# rf_bms.net
KiCad netlist of a schematic drawn in Altium Designer
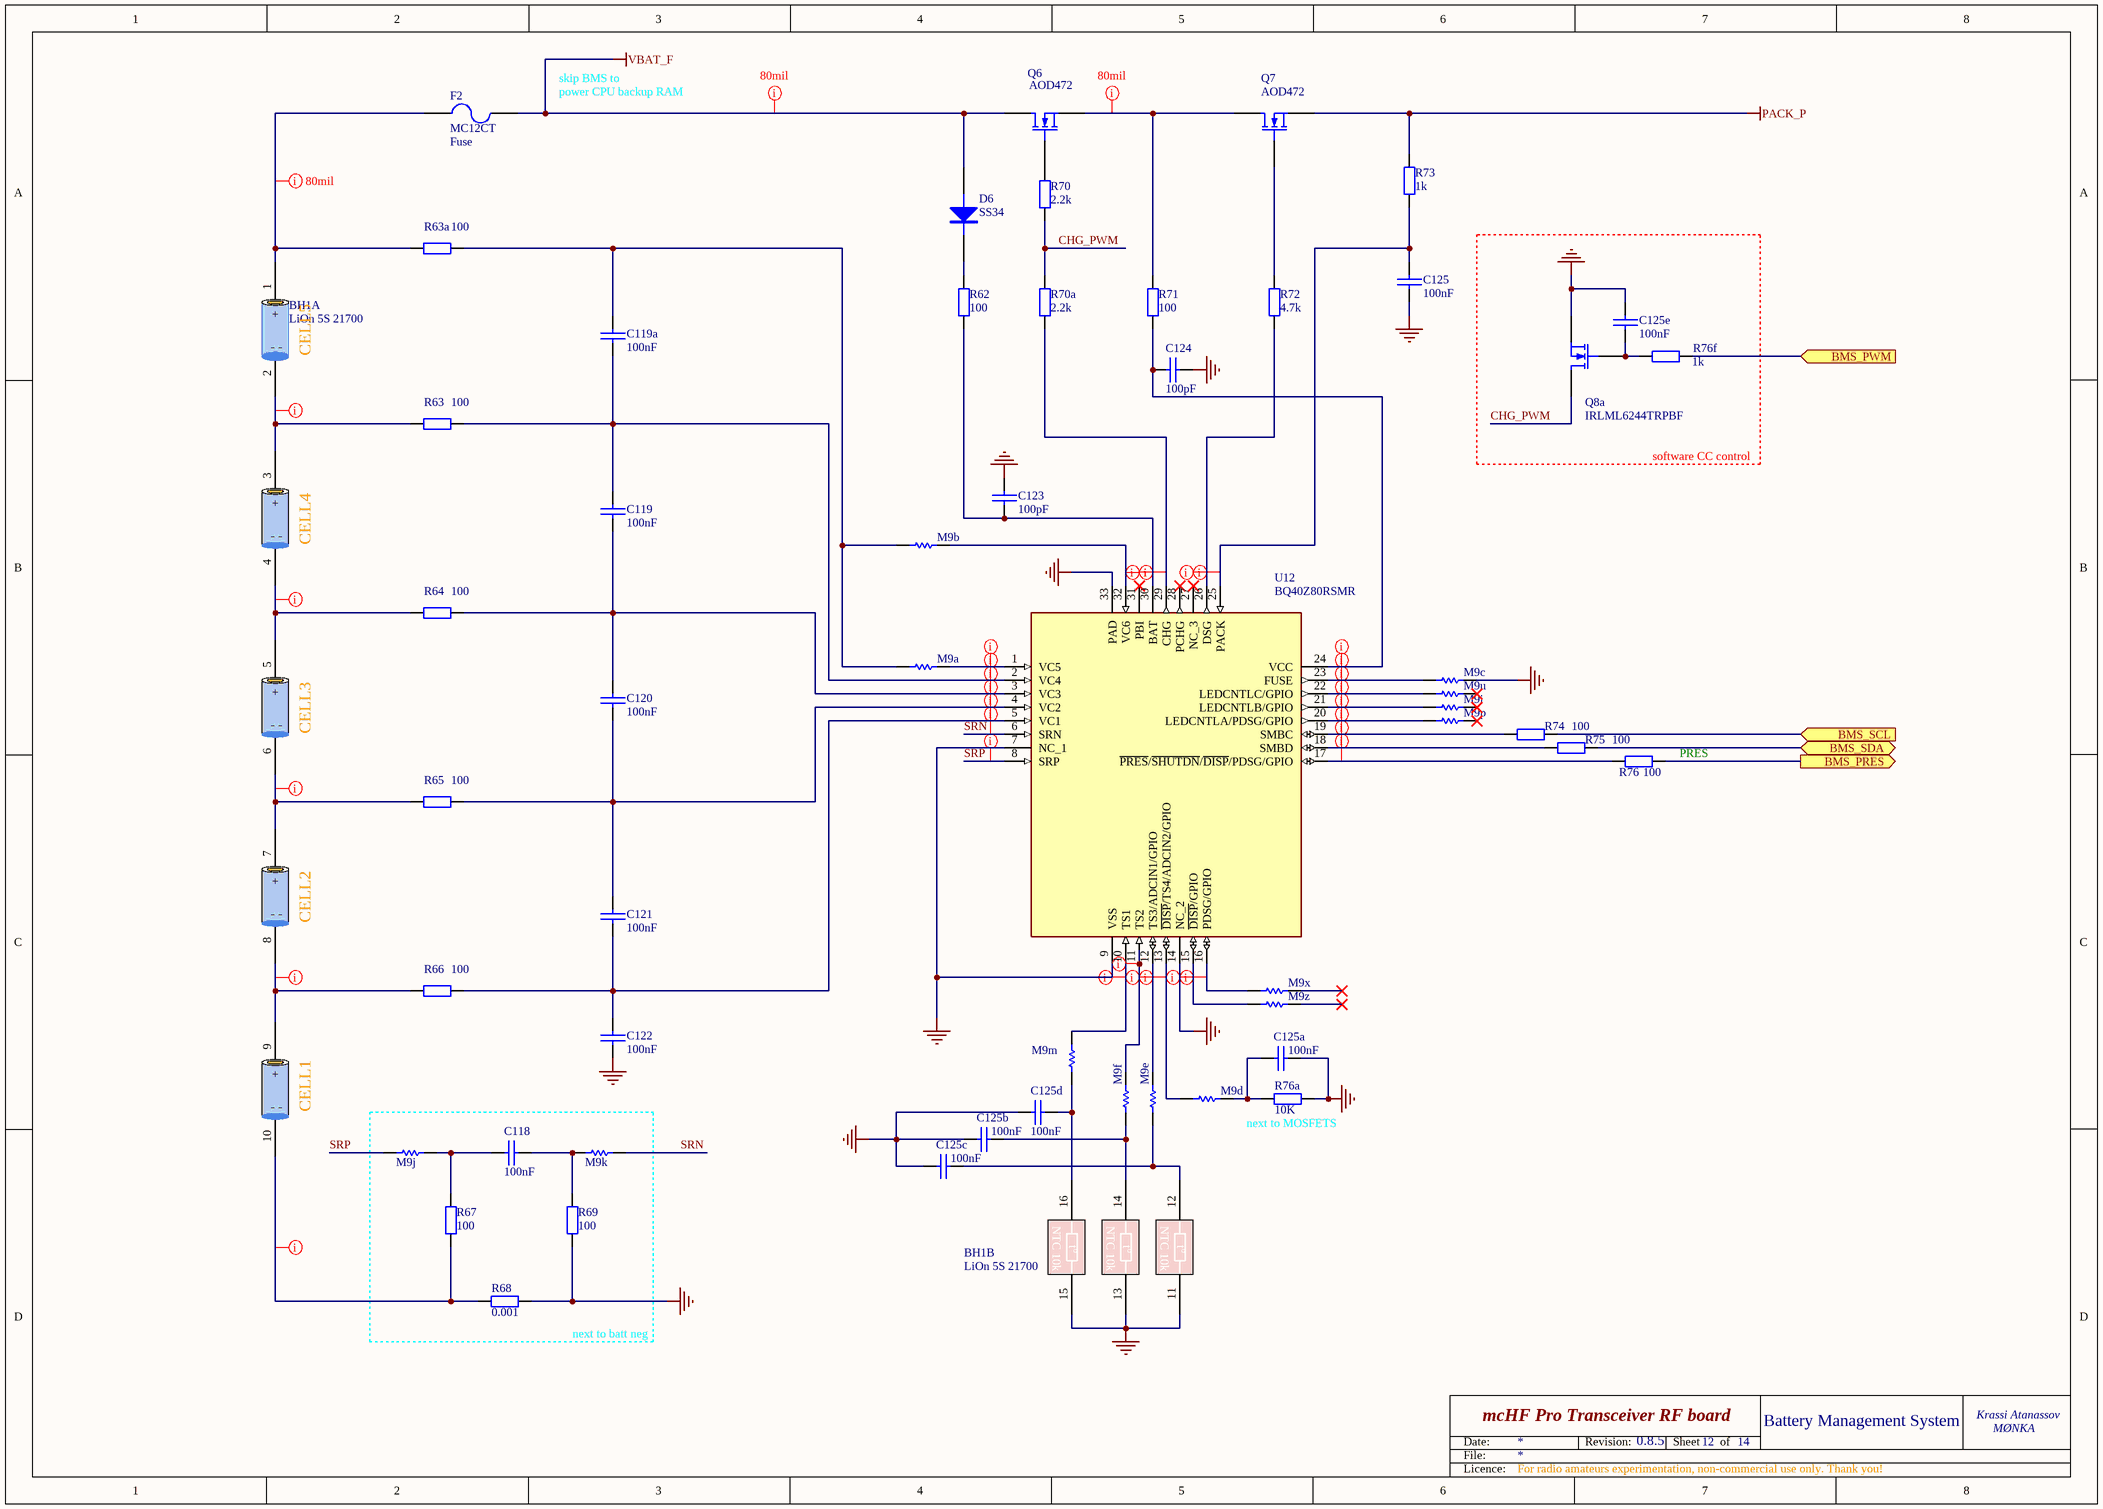
[diagram p0: rf_bms.SchDoc]

(export (version "E")
  (design (tool "Eeschema 10.0.6"))
  (components
    (comp (ref "BH1")
      (value "LiOn 5S 21700")
      (footprint "BATT_HOLDER_5S")
      (description "LiOn 21700 5S Holder")
      (libsource (lib "") (part "BATT_HOLDER_5S_21700_1"))
    )
    (comp (ref "C118")
      (value "100nF")
      (footprint "0805")
      (description "Capacitor")
      (fields (field (name "VOLTAGE") "100V"))
      (libsource (lib "mcHF_rf") (part "CAP"))
    )
    (comp (ref "C119")
      (value "100nF")
      (footprint "0805")
      (description "Capacitor")
      (fields (field (name "VOLTAGE") "100V"))
      (libsource (lib "mcHF_rf") (part "CAP"))
    )
    (comp (ref "C119a")
      (value "100nF")
      (footprint "0805")
      (description "Capacitor")
      (fields (field (name "VOLTAGE") "100V"))
      (libsource (lib "mcHF_rf") (part "CAP"))
    )
    (comp (ref "C120")
      (value "100nF")
      (footprint "0805")
      (description "Capacitor")
      (fields (field (name "VOLTAGE") "100V"))
      (libsource (lib "mcHF_rf") (part "CAP"))
    )
    (comp (ref "C121")
      (value "100nF")
      (footprint "0805")
      (description "Capacitor")
      (fields (field (name "VOLTAGE") "100V"))
      (libsource (lib "mcHF_rf") (part "CAP"))
    )
    (comp (ref "C122")
      (value "100nF")
      (footprint "0805")
      (description "Capacitor")
      (fields (field (name "VOLTAGE") "100V"))
      (libsource (lib "mcHF_rf") (part "CAP"))
    )
    (comp (ref "C123")
      (value "100pF")
      (footprint "0805")
      (description "Capacitor")
      (fields (field (name "VOLTAGE") "100V"))
      (libsource (lib "mcHF_rf") (part "CAP"))
    )
    (comp (ref "C124")
      (value "100pF")
      (footprint "0805")
      (description "Capacitor")
      (fields (field (name "VOLTAGE") "100V"))
      (libsource (lib "mcHF_rf") (part "CAP"))
    )
    (comp (ref "C125")
      (value "100nF")
      (footprint "0805")
      (description "Capacitor")
      (fields (field (name "VOLTAGE") "100V"))
      (libsource (lib "mcHF_rf") (part "CAP"))
    )
    (comp (ref "C125a")
      (value "100nF")
      (footprint "0805")
      (description "Capacitor")
      (fields (field (name "VOLTAGE") "100V"))
      (libsource (lib "mcHF_rf") (part "CAP"))
    )
    (comp (ref "C125b")
      (value "100nF")
      (footprint "0805")
      (description "Capacitor")
      (fields (field (name "VOLTAGE") "100V"))
      (libsource (lib "mcHF_rf") (part "CAP"))
    )
    (comp (ref "C125c")
      (value "100nF")
      (footprint "0805")
      (description "Capacitor")
      (fields (field (name "VOLTAGE") "100V"))
      (libsource (lib "mcHF_rf") (part "CAP"))
    )
    (comp (ref "C125d")
      (value "100nF")
      (footprint "0805")
      (description "Capacitor")
      (fields (field (name "VOLTAGE") "100V"))
      (libsource (lib "mcHF_rf") (part "CAP"))
    )
    (comp (ref "C125e")
      (value "100nF")
      (footprint "0805")
      (description "Capacitor")
      (fields (field (name "VOLTAGE") "100V"))
      (libsource (lib "mcHF_rf") (part "CAP"))
    )
    (comp (ref "D6")
      (value "SS34")
      (footprint "DO214")
      (description "DIODE, SCHOTTKY, 1A, 60V, SOD-123F")
      (libsource (lib "mcHF_rf") (part "PMEG6010CEH"))
    )
    (comp (ref "F2")
      (value "MC12CT")
      (footprint "1206")
      (description "Fuse")
      (fields (field (name "FUNCTION") "Fuse"))
      (libsource (lib "mcHF_rf") (part "Fuse"))
    )
    (comp (ref "M9a")
      (value "0")
      (footprint "SB_0603_10")
      (description "Link")
      (fields (field (name "PUBLISHER") "Altium Limited"))
      (libsource (lib "__ui") (part "Link"))
    )
    (comp (ref "M9b")
      (value "0")
      (footprint "SB_0603_10")
      (description "Link")
      (fields (field (name "PUBLISHER") "Altium Limited"))
      (libsource (lib "__ui") (part "Link"))
    )
    (comp (ref "M9c")
      (value "0")
      (footprint "SB_0603_10")
      (description "Link")
      (fields (field (name "PUBLISHER") "Altium Limited"))
      (libsource (lib "__ui") (part "Link"))
    )
    (comp (ref "M9d")
      (value "0")
      (footprint "SB_0603_10")
      (description "Link")
      (fields (field (name "PUBLISHER") "Altium Limited"))
      (libsource (lib "__ui") (part "Link"))
    )
    (comp (ref "M9e")
      (value "0")
      (footprint "SB_0603_10")
      (description "Link")
      (fields (field (name "PUBLISHER") "Altium Limited"))
      (libsource (lib "__ui") (part "Link"))
    )
    (comp (ref "M9f")
      (value "0")
      (footprint "SB_0603_10")
      (description "Link")
      (fields (field (name "PUBLISHER") "Altium Limited"))
      (libsource (lib "__ui") (part "Link"))
    )
    (comp (ref "M9i")
      (value "0")
      (footprint "SB_0603_10")
      (description "Link")
      (fields (field (name "PUBLISHER") "Altium Limited"))
      (libsource (lib "__ui") (part "Link"))
    )
    (comp (ref "M9j")
      (value "0")
      (footprint "SB_0603_10")
      (description "Link")
      (fields (field (name "PUBLISHER") "Altium Limited"))
      (libsource (lib "__ui") (part "Link"))
    )
    (comp (ref "M9k")
      (value "0")
      (footprint "SB_0603_10")
      (description "Link")
      (fields (field (name "PUBLISHER") "Altium Limited"))
      (libsource (lib "__ui") (part "Link"))
    )
    (comp (ref "M9m")
      (value "0")
      (footprint "SB_0603_10")
      (description "Link")
      (fields (field (name "PUBLISHER") "Altium Limited"))
      (libsource (lib "__ui") (part "Link"))
    )
    (comp (ref "M9p")
      (value "0")
      (footprint "SB_0603_10")
      (description "Link")
      (fields (field (name "PUBLISHER") "Altium Limited"))
      (libsource (lib "__ui") (part "Link"))
    )
    (comp (ref "M9u")
      (value "0")
      (footprint "SB_0603_10")
      (description "Link")
      (fields (field (name "PUBLISHER") "Altium Limited"))
      (libsource (lib "__ui") (part "Link"))
    )
    (comp (ref "M9x")
      (value "0")
      (footprint "SB_0603_10")
      (description "Link")
      (fields (field (name "PUBLISHER") "Altium Limited"))
      (libsource (lib "__ui") (part "Link"))
    )
    (comp (ref "M9z")
      (value "0")
      (footprint "SB_0603_10")
      (description "Link")
      (fields (field (name "PUBLISHER") "Altium Limited"))
      (libsource (lib "__ui") (part "Link"))
    )
    (comp (ref "Q6")
      (value "AOD472")
      (footprint "TO-252")
      (description "N-Channel Enhancement Mode Field Effect Transistor, TO-252")
      (libsource (lib "__rf") (part "AOD472"))
    )
    (comp (ref "Q7")
      (value "AOD472")
      (footprint "TO-252")
      (description "N-Channel Enhancement Mode Field Effect Transistor, TO-252")
      (libsource (lib "__rf") (part "AOD472"))
    )
    (comp (ref "Q8a")
      (value "IRLML6244TRPBF")
      (footprint "SOT-23-Pro")
      (description "N-Channel MOSFET")
      (libsource (lib "mcHF_ui_b") (part "MOSFET-N"))
    )
    (comp (ref "R62")
      (value "100")
      (footprint "0805")
      (description "Resistor")
      (libsource (lib "mcHF_rf") (part "RES"))
    )
    (comp (ref "R63")
      (value "100")
      (footprint "0805")
      (description "Resistor")
      (libsource (lib "") (part "RES_2"))
    )
    (comp (ref "R63a")
      (value "100")
      (footprint "0805")
      (description "Resistor")
      (libsource (lib "") (part "RES_2"))
    )
    (comp (ref "R64")
      (value "100")
      (footprint "0805")
      (description "Resistor")
      (libsource (lib "") (part "RES_2"))
    )
    (comp (ref "R65")
      (value "100")
      (footprint "0805")
      (description "Resistor")
      (libsource (lib "") (part "RES_2"))
    )
    (comp (ref "R66")
      (value "100")
      (footprint "0805")
      (description "Resistor")
      (libsource (lib "") (part "RES_2"))
    )
    (comp (ref "R67")
      (value "100")
      (footprint "0805")
      (description "Resistor")
      (libsource (lib "mcHF_ui_b") (part "RES"))
    )
    (comp (ref "R68")
      (value "0.001")
      (footprint "2512")
      (description "Resistor")
      (libsource (lib "") (part "RES_1"))
    )
    (comp (ref "R69")
      (value "100")
      (footprint "0805")
      (description "Resistor")
      (libsource (lib "mcHF_ui_b") (part "RES"))
    )
    (comp (ref "R70")
      (value "2.2k")
      (footprint "0805")
      (description "Resistor")
      (libsource (lib "") (part "RES_1"))
    )
    (comp (ref "R70a")
      (value "2.2k")
      (footprint "0805")
      (description "Resistor")
      (libsource (lib "") (part "RES_1"))
    )
    (comp (ref "R71")
      (value "100")
      (footprint "0805")
      (description "Resistor")
      (libsource (lib "mcHF_ui_b") (part "RES"))
    )
    (comp (ref "R72")
      (value "4.7k")
      (footprint "0805")
      (description "Resistor")
      (libsource (lib "") (part "RES_1"))
    )
    (comp (ref "R73")
      (value "1k")
      (footprint "0805")
      (description "Resistor")
      (libsource (lib "") (part "RES_1"))
    )
    (comp (ref "R74")
      (value "100")
      (footprint "0805")
      (description "Resistor")
      (libsource (lib "") (part "RES_2"))
    )
    (comp (ref "R75")
      (value "100")
      (footprint "0805")
      (description "Resistor")
      (libsource (lib "") (part "RES_2"))
    )
    (comp (ref "R76")
      (value "100")
      (footprint "0805")
      (description "Resistor")
      (libsource (lib "") (part "RES_2"))
    )
    (comp (ref "R76a")
      (value "10K")
      (footprint "0805")
      (description "Resistor")
      (libsource (lib "") (part "RES_1"))
    )
    (comp (ref "R76f")
      (value "1k")
      (footprint "0805")
      (description "Resistor")
      (libsource (lib "") (part "RES_2"))
    )
    (comp (ref "U12")
      (value "BQ40Z80RSMR")
      (footprint "SamacSys:QFN40P400X400X100-33N-D")
      (description "Hardware")
      (fields (field (name "MOUSER PART NUMBER") "595-BQ40Z80RSMR"))
      (libsource (lib "SamacSys") (part "BQ40Z80RSMR"))
    )
  )
  (nets
    (net (code "1") (name "/BMS_PRES") (class "Default")
      (node (ref "R76") (pin "2") (pinfunction "2_2") (pintype "passive"))
    )
    (net (code "2") (name "/BMS_PWM") (class "Default")
      (node (ref "R76f") (pin "2") (pinfunction "2_2") (pintype "passive"))
    )
    (net (code "3") (name "/BMS_SCL") (class "Default")
      (node (ref "R74") (pin "2") (pinfunction "2_2") (pintype "passive"))
    )
    (net (code "4") (name "/BMS_SDA") (class "Default")
      (node (ref "R75") (pin "2") (pinfunction "2_2") (pintype "passive"))
    )
    (net (code "5") (name "/CHG_PWM") (class "Default")
      (node (ref "Q8a") (pin "3") (pinfunction "D_3") (pintype "passive"))
      (node (ref "R70") (pin "1") (pinfunction "1_1") (pintype "passive"))
      (node (ref "R70a") (pin "2") (pinfunction "2_2") (pintype "passive"))
    )
    (net (code "6") (name "/SRN") (class "Default")
      (node (ref "M9k") (pin "1") (pinfunction "1_1") (pintype "passive"))
      (node (ref "U12") (pin "6") (pinfunction "SRN_6") (pintype "input"))
    )
    (net (code "7") (name "/SRP") (class "Default")
      (node (ref "M9j") (pin "2") (pinfunction "2_2") (pintype "passive"))
      (node (ref "U12") (pin "8") (pinfunction "SRP_8") (pintype "input"))
    )
    (net (code "8") (name "GND") (class "Default")
      (node (ref "BH1") (pin "11") (pintype "passive"))
      (node (ref "BH1") (pin "13") (pintype "passive"))
      (node (ref "BH1") (pin "15") (pintype "passive"))
      (node (ref "C122") (pin "2") (pinfunction "2_2") (pintype "passive"))
      (node (ref "C123") (pin "1") (pinfunction "1_1") (pintype "passive"))
      (node (ref "C124") (pin "1") (pinfunction "1_1") (pintype "passive"))
      (node (ref "C125") (pin "2") (pinfunction "2_2") (pintype "passive"))
      (node (ref "C125a") (pin "1") (pinfunction "1_1") (pintype "passive"))
      (node (ref "C125b") (pin "2") (pinfunction "2_2") (pintype "passive"))
      (node (ref "C125c") (pin "2") (pinfunction "2_2") (pintype "passive"))
      (node (ref "C125d") (pin "2") (pinfunction "2_2") (pintype "passive"))
      (node (ref "C125e") (pin "2") (pinfunction "2_2") (pintype "passive"))
      (node (ref "M9c") (pin "2") (pinfunction "2_2") (pintype "passive"))
      (node (ref "Q8a") (pin "2") (pinfunction "S_2") (pintype "passive"))
      (node (ref "R68") (pin "2") (pinfunction "2_2") (pintype "passive"))
      (node (ref "R69") (pin "2") (pinfunction "2_2") (pintype "passive"))
      (node (ref "R76a") (pin "2") (pinfunction "2_2") (pintype "passive"))
      (node (ref "U12") (pin "14") (pinfunction "NC_2_14") (pintype "passive"))
      (node (ref "U12") (pin "33") (pinfunction "PAD_33") (pintype "power_in"))
      (node (ref "U12") (pin "7") (pinfunction "NC_1_7") (pintype "passive"))
      (node (ref "U12") (pin "9") (pinfunction "VSS_9") (pintype "power_in"))
    )
    (net (code "9") (name "Net-(BH1-Pad12)") (class "Default")
      (node (ref "BH1") (pin "12") (pintype "passive"))
      (node (ref "C125c") (pin "1") (pinfunction "1_1") (pintype "passive"))
      (node (ref "M9e") (pin "2") (pinfunction "2_2") (pintype "passive"))
    )
    (net (code "10") (name "Net-(BH1-Pad14)") (class "Default")
      (node (ref "BH1") (pin "14") (pintype "passive"))
      (node (ref "C125b") (pin "1") (pinfunction "1_1") (pintype "passive"))
      (node (ref "M9f") (pin "2") (pinfunction "2_2") (pintype "passive"))
    )
    (net (code "11") (name "Net-(BH1-Pad16)") (class "Default")
      (node (ref "BH1") (pin "16") (pintype "passive"))
      (node (ref "C125d") (pin "1") (pinfunction "1_1") (pintype "passive"))
      (node (ref "M9m") (pin "1") (pinfunction "1_1") (pintype "passive"))
    )
    (net (code "12") (name "Net-(BH1A-+-Pad1)") (class "Default")
      (node (ref "BH1") (pin "1") (pinfunction "+_1") (pintype "passive"))
      (node (ref "F2") (pin "1") (pinfunction "1_1") (pintype "passive"))
      (node (ref "R63a") (pin "2") (pinfunction "2_2") (pintype "passive"))
    )
    (net (code "13") (name "Net-(BH1A-+-Pad3)") (class "Default")
      (node (ref "BH1") (pin "2") (pinfunction "¦_2") (pintype "passive"))
      (node (ref "BH1") (pin "3") (pinfunction "+_3") (pintype "passive"))
      (node (ref "R63") (pin "2") (pinfunction "2_2") (pintype "passive"))
    )
    (net (code "14") (name "Net-(BH1A-+-Pad5)") (class "Default")
      (node (ref "BH1") (pin "4") (pinfunction "¦_4") (pintype "passive"))
      (node (ref "BH1") (pin "5") (pinfunction "+_5") (pintype "passive"))
      (node (ref "R64") (pin "2") (pinfunction "2_2") (pintype "passive"))
    )
    (net (code "15") (name "Net-(BH1A-+-Pad7)") (class "Default")
      (node (ref "BH1") (pin "6") (pinfunction "¦_6") (pintype "passive"))
      (node (ref "BH1") (pin "7") (pinfunction "+_7") (pintype "passive"))
      (node (ref "R65") (pin "2") (pinfunction "2_2") (pintype "passive"))
    )
    (net (code "16") (name "Net-(BH1A-+-Pad9)") (class "Default")
      (node (ref "BH1") (pin "8") (pinfunction "¦_8") (pintype "passive"))
      (node (ref "BH1") (pin "9") (pinfunction "+_9") (pintype "passive"))
      (node (ref "R66") (pin "2") (pinfunction "2_2") (pintype "passive"))
    )
    (net (code "17") (name "Net-(BH1A-¦-Pad10)") (class "Default")
      (node (ref "BH1") (pin "10") (pinfunction "¦_10") (pintype "passive"))
      (node (ref "R67") (pin "2") (pinfunction "2_2") (pintype "passive"))
      (node (ref "R68") (pin "1") (pinfunction "1_1") (pintype "passive"))
    )
    (net (code "18") (name "Net-(C118-Pad1)") (class "Default")
      (node (ref "C118") (pin "1") (pinfunction "1_1") (pintype "passive"))
      (node (ref "M9k") (pin "2") (pinfunction "2_2") (pintype "passive"))
      (node (ref "R69") (pin "1") (pinfunction "1_1") (pintype "passive"))
    )
    (net (code "19") (name "Net-(C118-Pad2)") (class "Default")
      (node (ref "C118") (pin "2") (pinfunction "2_2") (pintype "passive"))
      (node (ref "M9j") (pin "1") (pinfunction "1_1") (pintype "passive"))
      (node (ref "R67") (pin "1") (pinfunction "1_1") (pintype "passive"))
    )
    (net (code "20") (name "Net-(C119a-Pad1)") (class "Default")
      (node (ref "C119a") (pin "1") (pinfunction "1_1") (pintype "passive"))
      (node (ref "M9a") (pin "1") (pinfunction "1_1") (pintype "passive"))
      (node (ref "M9b") (pin "1") (pinfunction "1_1") (pintype "passive"))
      (node (ref "R63a") (pin "1") (pinfunction "1_1") (pintype "passive"))
    )
    (net (code "21") (name "Net-(C125a-Pad2)") (class "Default")
      (node (ref "C125a") (pin "2") (pinfunction "2_2") (pintype "passive"))
      (node (ref "M9d") (pin "2") (pinfunction "2_2") (pintype "passive"))
      (node (ref "R76a") (pin "1") (pinfunction "1_1") (pintype "passive"))
    )
    (net (code "22") (name "Net-(D6-K)") (class "Default")
      (node (ref "D6") (pin "2") (pinfunction "K_2") (pintype "passive"))
      (node (ref "R62") (pin "2") (pinfunction "2_2") (pintype "passive"))
    )
    (net (code "23") (name "Net-(Q6-G)") (class "Default")
      (node (ref "Q6") (pin "1") (pinfunction "G_1") (pintype "passive"))
      (node (ref "R70") (pin "2") (pinfunction "2_2") (pintype "passive"))
    )
    (net (code "24") (name "Net-(Q6-S)") (class "Default")
      (node (ref "Q6") (pin "3") (pinfunction "S_3") (pintype "passive"))
      (node (ref "Q7") (pin "2") (pinfunction "D_2") (pintype "passive"))
      (node (ref "R71") (pin "1") (pinfunction "1_1") (pintype "passive"))
    )
    (net (code "25") (name "Net-(Q7-G)") (class "Default")
      (node (ref "Q7") (pin "1") (pinfunction "G_1") (pintype "passive"))
      (node (ref "R72") (pin "2") (pinfunction "2_2") (pintype "passive"))
    )
    (net (code "26") (name "Net-(Q8a-G)") (class "Default")
      (node (ref "C125e") (pin "1") (pinfunction "1_1") (pintype "passive"))
      (node (ref "Q8a") (pin "1") (pinfunction "G_1") (pintype "passive"))
      (node (ref "R76f") (pin "1") (pinfunction "1_1") (pintype "passive"))
    )
    (net (code "27") (name "Net-(U12-BAT)") (class "Default")
      (node (ref "C123") (pin "2") (pinfunction "2_2") (pintype "passive"))
      (node (ref "R62") (pin "1") (pinfunction "1_1") (pintype "passive"))
      (node (ref "U12") (pin "30") (pinfunction "BAT_30") (pintype "power_in"))
    )
    (net (code "28") (name "Net-(U12-CHG)") (class "Default")
      (node (ref "R70a") (pin "1") (pinfunction "1_1") (pintype "passive"))
      (node (ref "U12") (pin "29") (pinfunction "CHG_29") (pintype "output"))
    )
    (net (code "29") (name "Net-(U12-DSG)") (class "Default")
      (node (ref "R72") (pin "1") (pinfunction "1_1") (pintype "passive"))
      (node (ref "U12") (pin "26") (pinfunction "DSG_26") (pintype "output"))
    )
    (net (code "30") (name "Net-(U12-FUSE)") (class "Default")
      (node (ref "M9c") (pin "1") (pinfunction "1_1") (pintype "passive"))
      (node (ref "U12") (pin "23") (pinfunction "FUSE_23") (pintype "output"))
    )
    (net (code "31") (name "Net-(U12-LEDCNTLA{slash}PDSG{slash}GPIO)") (class "Default")
      (node (ref "M9p") (pin "1") (pinfunction "1_1") (pintype "passive"))
      (node (ref "U12") (pin "20") (pinfunction "LEDCNTLA/PDSG/GPIO_20") (pintype "output"))
    )
    (net (code "32") (name "Net-(U12-LEDCNTLB{slash}GPIO)") (class "Default")
      (node (ref "M9i") (pin "1") (pinfunction "1_1") (pintype "passive"))
      (node (ref "U12") (pin "21") (pinfunction "LEDCNTLB/GPIO_21") (pintype "output"))
    )
    (net (code "33") (name "Net-(U12-LEDCNTLC{slash}GPIO)") (class "Default")
      (node (ref "M9u") (pin "1") (pinfunction "1_1") (pintype "passive"))
      (node (ref "U12") (pin "22") (pinfunction "LEDCNTLC/GPIO_22") (pintype "output"))
    )
    (net (code "34") (name "Net-(U12-PACK)") (class "Default")
      (node (ref "C125") (pin "1") (pinfunction "1_1") (pintype "passive"))
      (node (ref "R73") (pin "1") (pinfunction "1_1") (pintype "passive"))
      (node (ref "U12") (pin "25") (pinfunction "PACK_25") (pintype "input"))
    )
    (net (code "35") (name "Net-(U12-PDSG{slash}GPIO)") (class "Default")
      (node (ref "M9x") (pin "1") (pinfunction "1_1") (pintype "passive"))
      (node (ref "U12") (pin "16") (pinfunction "PDSG/GPIO_16") (pintype "bidirectional"))
    )
    (net (code "36") (name "Net-(U12-SMBC)") (class "Default")
      (node (ref "R74") (pin "1") (pinfunction "1_1") (pintype "passive"))
      (node (ref "U12") (pin "19") (pinfunction "SMBC_19") (pintype "bidirectional"))
    )
    (net (code "37") (name "Net-(U12-SMBD)") (class "Default")
      (node (ref "R75") (pin "1") (pinfunction "1_1") (pintype "passive"))
      (node (ref "U12") (pin "18") (pinfunction "SMBD_18") (pintype "bidirectional"))
    )
    (net (code "38") (name "Net-(U12-TS1)") (class "Default")
      (node (ref "M9m") (pin "2") (pinfunction "2_2") (pintype "passive"))
      (node (ref "U12") (pin "10") (pinfunction "TS1_10") (pintype "input"))
    )
    (net (code "39") (name "Net-(U12-TS2)") (class "Default")
      (node (ref "M9f") (pin "1") (pinfunction "1_1") (pintype "passive"))
      (node (ref "U12") (pin "11") (pinfunction "TS2_11") (pintype "input"))
    )
    (net (code "40") (name "Net-(U12-TS3{slash}ADCIN1{slash}GPIO)") (class "Default")
      (node (ref "M9e") (pin "1") (pinfunction "1_1") (pintype "passive"))
      (node (ref "U12") (pin "12") (pinfunction "TS3/ADCIN1/GPIO_12") (pintype "bidirectional"))
    )
    (net (code "41") (name "Net-(U12-VC1)") (class "Default")
      (node (ref "C121") (pin "2") (pinfunction "2_2") (pintype "passive"))
      (node (ref "C122") (pin "1") (pinfunction "1_1") (pintype "passive"))
      (node (ref "R66") (pin "1") (pinfunction "1_1") (pintype "passive"))
      (node (ref "U12") (pin "5") (pinfunction "VC1_5") (pintype "input"))
    )
    (net (code "42") (name "Net-(U12-VC2)") (class "Default")
      (node (ref "C120") (pin "2") (pinfunction "2_2") (pintype "passive"))
      (node (ref "C121") (pin "1") (pinfunction "1_1") (pintype "passive"))
      (node (ref "R65") (pin "1") (pinfunction "1_1") (pintype "passive"))
      (node (ref "U12") (pin "4") (pinfunction "VC2_4") (pintype "input"))
    )
    (net (code "43") (name "Net-(U12-VC3)") (class "Default")
      (node (ref "C119") (pin "2") (pinfunction "2_2") (pintype "passive"))
      (node (ref "C120") (pin "1") (pinfunction "1_1") (pintype "passive"))
      (node (ref "R64") (pin "1") (pinfunction "1_1") (pintype "passive"))
      (node (ref "U12") (pin "3") (pinfunction "VC3_3") (pintype "input"))
    )
    (net (code "44") (name "Net-(U12-VC4)") (class "Default")
      (node (ref "C119") (pin "1") (pinfunction "1_1") (pintype "passive"))
      (node (ref "C119a") (pin "2") (pinfunction "2_2") (pintype "passive"))
      (node (ref "R63") (pin "1") (pinfunction "1_1") (pintype "passive"))
      (node (ref "U12") (pin "2") (pinfunction "VC4_2") (pintype "input"))
    )
    (net (code "45") (name "Net-(U12-VC5)") (class "Default")
      (node (ref "M9a") (pin "2") (pinfunction "2_2") (pintype "passive"))
      (node (ref "U12") (pin "1") (pinfunction "VC5_1") (pintype "input"))
    )
    (net (code "46") (name "Net-(U12-VC6)") (class "Default")
      (node (ref "M9b") (pin "2") (pinfunction "2_2") (pintype "passive"))
      (node (ref "U12") (pin "32") (pinfunction "VC6_32") (pintype "input"))
    )
    (net (code "47") (name "Net-(U12-VCC)") (class "Default")
      (node (ref "C124") (pin "2") (pinfunction "2_2") (pintype "passive"))
      (node (ref "R71") (pin "2") (pinfunction "2_2") (pintype "passive"))
      (node (ref "U12") (pin "24") (pinfunction "VCC_24") (pintype "power_in"))
    )
    (net (code "48") (name "Net-(U12-~{DISP}{slash}GPIO)") (class "Default")
      (node (ref "M9z") (pin "1") (pinfunction "1_1") (pintype "passive"))
      (node (ref "U12") (pin "15") (pinfunction "~{DISP}/GPIO_15") (pintype "bidirectional"))
    )
    (net (code "49") (name "Net-(U12-~{DISP}{slash}TS4{slash}ADCIN2{slash}GPIO)") (class "Default")
      (node (ref "M9d") (pin "1") (pinfunction "1_1") (pintype "passive"))
      (node (ref "U12") (pin "13") (pinfunction "~{DISP}/TS4/ADCIN2/GPIO_13") (pintype "bidirectional"))
    )
    (net (code "50") (name "Net-(U12-~{PRES}{slash}~{SHUTDN}{slash}~{DISP}{slash}PDSG{slash}GPIO)") (class "Default")
      (node (ref "R76") (pin "1") (pinfunction "1_1") (pintype "passive"))
      (node (ref "U12") (pin "17") (pinfunction "~{PRES}/~{SHUTDN}/~{DISP}/PDSG/GPIO_17") (pintype "bidirectional"))
    )
    (net (code "51") (name "PACK_P") (class "Default")
      (node (ref "Q7") (pin "3") (pinfunction "S_3") (pintype "passive"))
      (node (ref "R73") (pin "2") (pinfunction "2_2") (pintype "passive"))
    )
    (net (code "52") (name "VBAT_F") (class "Default")
      (node (ref "D6") (pin "1") (pinfunction "A_1") (pintype "passive"))
      (node (ref "F2") (pin "2") (pinfunction "2_2") (pintype "passive"))
      (node (ref "Q6") (pin "2") (pinfunction "D_2") (pintype "passive"))
    )
    (net (code "53") (name "unconnected-(M9i-Pad2)") (class "Default")
      (node (ref "M9i") (pin "2") (pinfunction "2_2") (pintype "passive+no_connect"))
    )
    (net (code "54") (name "unconnected-(M9p-Pad2)") (class "Default")
      (node (ref "M9p") (pin "2") (pinfunction "2_2") (pintype "passive+no_connect"))
    )
    (net (code "55") (name "unconnected-(M9u-Pad2)") (class "Default")
      (node (ref "M9u") (pin "2") (pinfunction "2_2") (pintype "passive+no_connect"))
    )
    (net (code "56") (name "unconnected-(M9x-Pad2)") (class "Default")
      (node (ref "M9x") (pin "2") (pinfunction "2_2") (pintype "passive+no_connect"))
    )
    (net (code "57") (name "unconnected-(M9z-Pad2)") (class "Default")
      (node (ref "M9z") (pin "2") (pinfunction "2_2") (pintype "passive+no_connect"))
    )
    (net (code "58") (name "unconnected-(U12-NC_3-Pad27)") (class "Default")
      (node (ref "U12") (pin "27") (pinfunction "NC_3_27") (pintype "passive+no_connect"))
    )
    (net (code "59") (name "unconnected-(U12-PBI-Pad31)") (class "Default")
      (node (ref "U12") (pin "31") (pinfunction "PBI_31") (pintype "power_in+no_connect"))
    )
    (net (code "60") (name "unconnected-(U12-PCHG-Pad28)") (class "Default")
      (node (ref "U12") (pin "28") (pinfunction "PCHG_28") (pintype "output+no_connect"))
    )
  )
)
